# Garden_Solar_Lights_rev_a.net
KiCad netlist of a schematic drawn in EAGLE
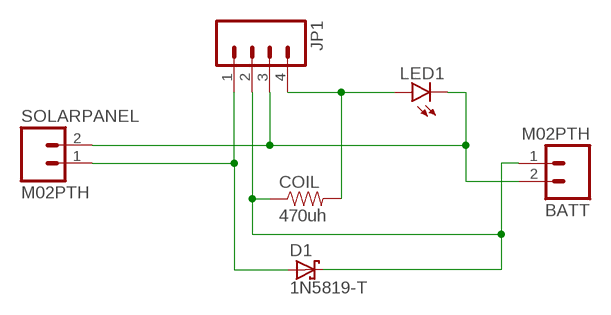
[diagram p0: schematic, sheet 1]

(export (version "E")
  (design (tool "Eeschema 10.0.6"))
  (components
    (comp (ref "BATT")
      (value "M02PTH")
      (footprint "eagle-import:1X02")
      (libsource (lib "eagle-import") (part "M02PTH"))
    )
    (comp (ref "COIL")
      (value "470uh")
      (footprint "eagle-import:AXIAL-0.5")
      (libsource (lib "eagle-import") (part "RESISTORPTH-1/2W"))
    )
    (comp (ref "D1")
      (value "1N5819-T")
      (footprint "eagle-import:DO41-7.6")
      (libsource (lib "eagle-import") (part "1N5819-T"))
    )
    (comp (ref "JP1")
      (value "M04PTH")
      (footprint "eagle-import:1X04")
      (libsource (lib "eagle-import") (part "M04PTH"))
    )
    (comp (ref "LED1")
      (value "LED3MM")
      (footprint "eagle-import:LED3MM")
      (libsource (lib "eagle-import") (part "LED3MM"))
    )
    (comp (ref "SOLARPANEL")
      (value "M02PTH")
      (footprint "eagle-import:1X02")
      (libsource (lib "eagle-import") (part "M02PTH"))
    )
  )
  (nets
    (net (code "1") (name "Net-(COIL-1)") (class "Default")
      (node (ref "BATT") (pin "1") (pinfunction "1_1") (pintype "passive"))
      (node (ref "COIL") (pin "P$1") (pinfunction "1_P$1") (pintype "passive"))
      (node (ref "D1") (pin "C") (pinfunction "C_C") (pintype "passive"))
      (node (ref "JP1") (pin "2") (pinfunction "2_2") (pintype "passive"))
    )
    (net (code "2") (name "Net-(COIL-2)") (class "Default")
      (node (ref "COIL") (pin "P$2") (pinfunction "2_P$2") (pintype "passive"))
      (node (ref "JP1") (pin "4") (pinfunction "4_4") (pintype "passive"))
      (node (ref "LED1") (pin "A") (pinfunction "A_A") (pintype "passive"))
    )
    (net (code "3") (name "Net-(D1-PadA)") (class "Default")
      (node (ref "D1") (pin "A") (pinfunction "A_A") (pintype "passive"))
      (node (ref "JP1") (pin "1") (pinfunction "1_1") (pintype "passive"))
      (node (ref "SOLARPANEL") (pin "1") (pinfunction "1_1") (pintype "passive"))
    )
    (net (code "4") (name "Net-(LED1-C)") (class "Default")
      (node (ref "BATT") (pin "2") (pinfunction "2_2") (pintype "passive"))
      (node (ref "JP1") (pin "3") (pinfunction "3_3") (pintype "passive"))
      (node (ref "LED1") (pin "K") (pinfunction "C_K") (pintype "passive"))
      (node (ref "SOLARPANEL") (pin "2") (pinfunction "2_2") (pintype "passive"))
    )
  )
)
